# eCog102_uSD.net
KiCad netlist of a schematic drawn in EAGLE
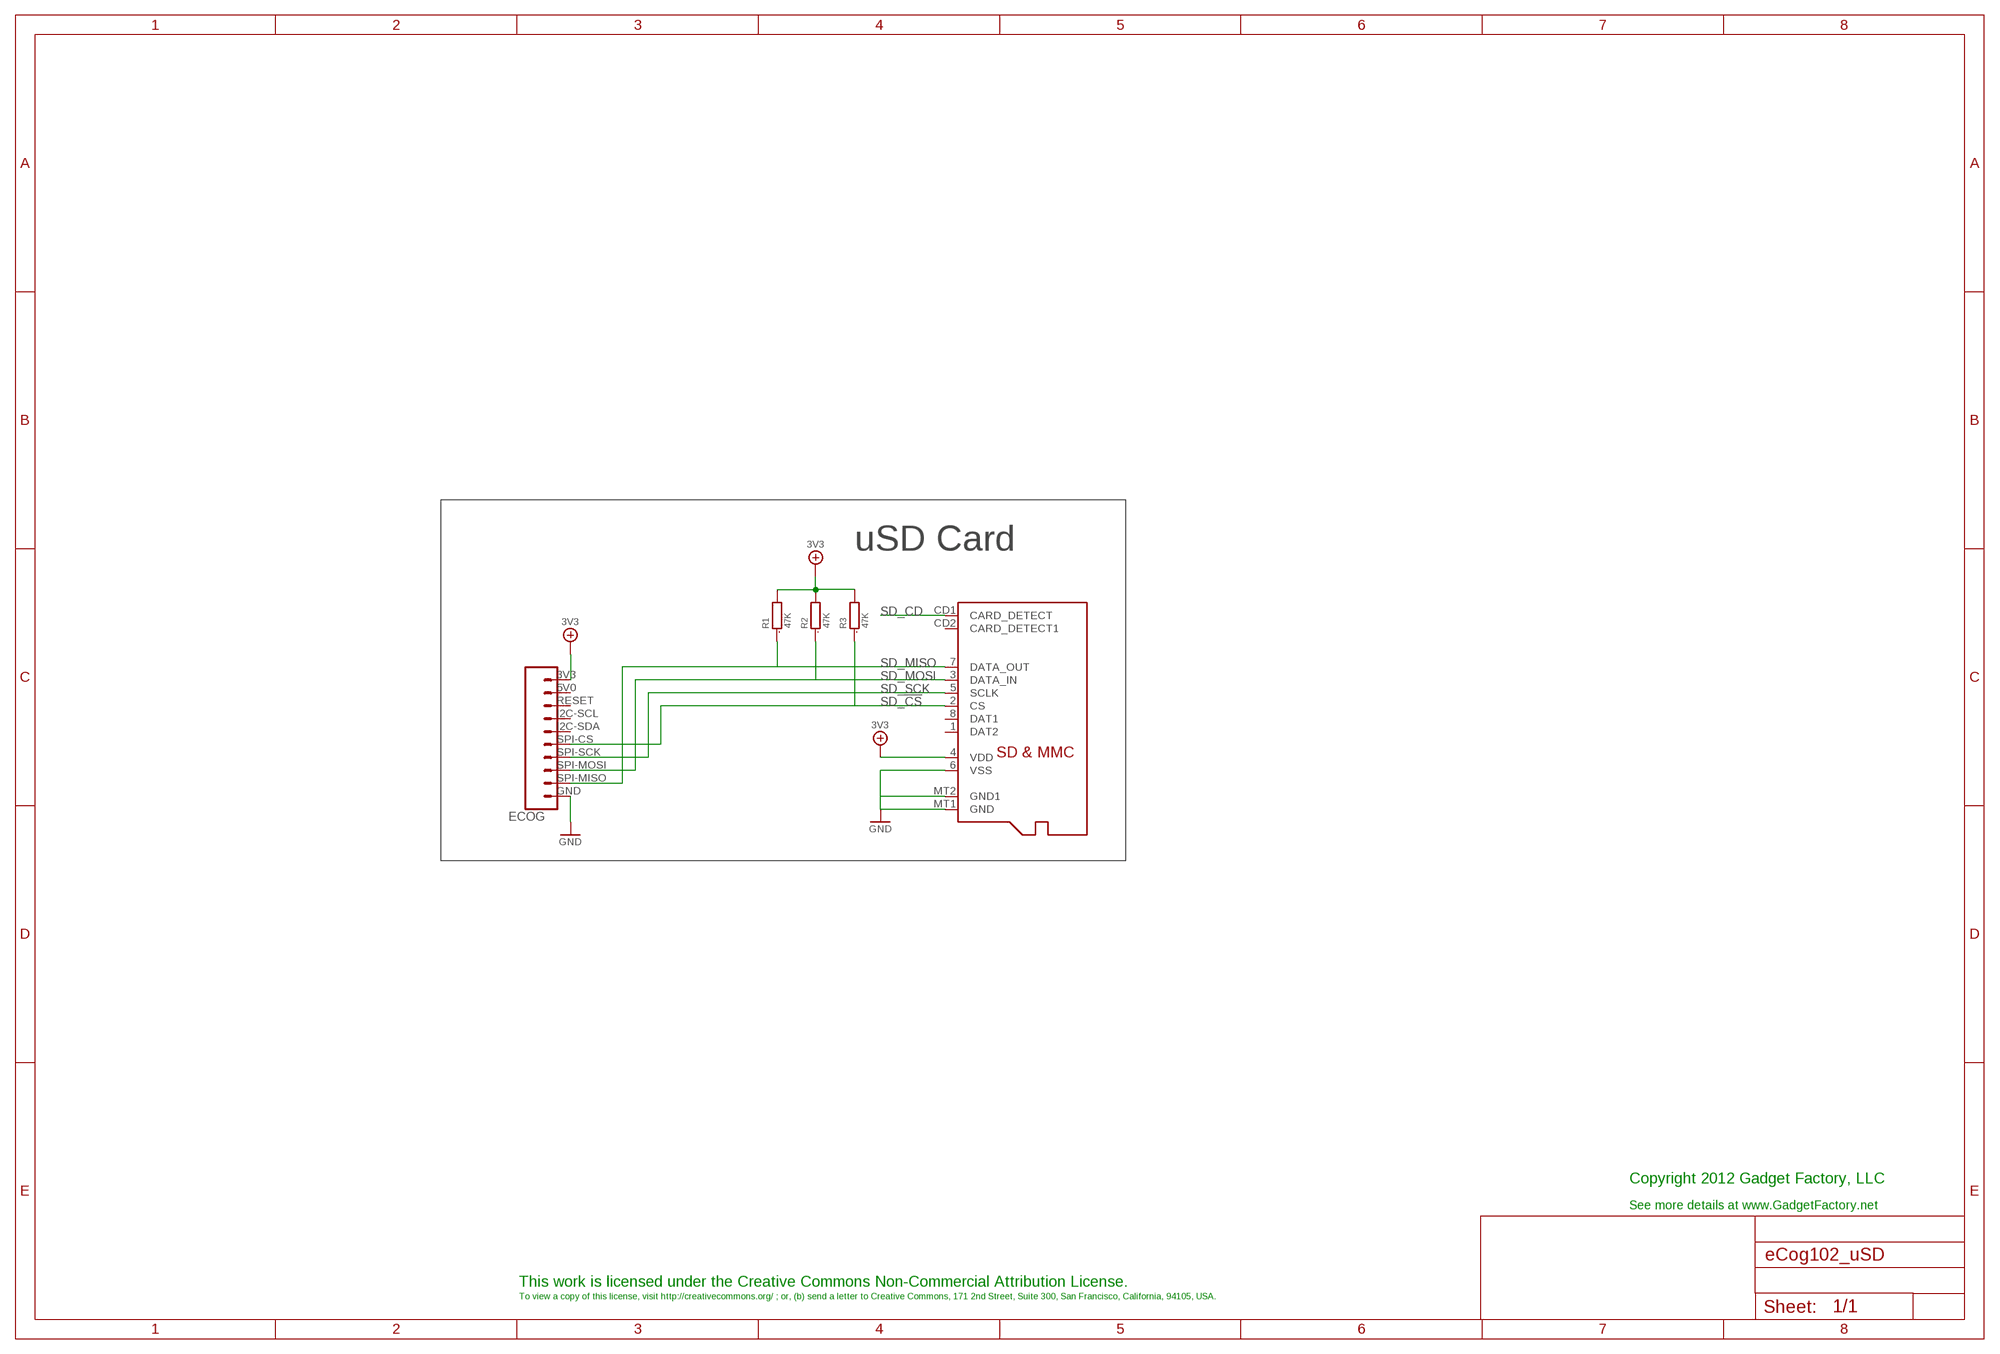
[diagram p0: schematic, sheet 1]

(export (version "E")
  (design (tool "Eeschema 10.0.6"))
  (components
    (comp (ref "ECOG")
      (value "ECOG_BUSES_ROWECOG_BUSES_SMD")
      (footprint "eagle-import:ECOG_BUSES_SMD")
      (libsource (lib "eagle-import") (part "ECOG_BUSES_ROWECOG_BUSES_SMD"))
    )
    (comp (ref "R1")
      (value "47K")
      (footprint "eagle-import:0805")
      (fields (field (name "PARTNO") "RMCF0805JT47K0"))
      (libsource (lib "eagle-import") (part "R0805"))
    )
    (comp (ref "R2")
      (value "47K")
      (footprint "eagle-import:0805")
      (fields (field (name "PARTNO") "RMCF0805JT47K0"))
      (libsource (lib "eagle-import") (part "R0805"))
    )
    (comp (ref "R3")
      (value "47K")
      (footprint "eagle-import:0805")
      (fields (field (name "PARTNO") "RMCF0805JT47K0"))
      (libsource (lib "eagle-import") (part "R0805"))
    )
    (comp (ref "SD1")
      (value "MICROSD")
      (footprint "eagle-import:MICROSD")
      (fields (field (name "DIGIKEY") "101-00660-68-6-1-ND") (field (name "PARTNO") "101-00660-68-6"))
      (libsource (lib "eagle-import") (part "MICROSD"))
    )
  )
  (nets
    (net (code "1") (name "/SD_CD") (class "Default")
      (node (ref "SD1") (pin "CD1") (pinfunction "CARD_DETECT_CD1") (pintype "passive"))
    )
    (net (code "2") (name "/SD_MISO") (class "Default")
      (node (ref "ECOG") (pin "SPI-MISO") (pinfunction "SPI-MISO_SPI-MISO") (pintype "passive"))
      (node (ref "R1") (pin "1") (pinfunction "1_1") (pintype "passive"))
      (node (ref "SD1") (pin "7") (pinfunction "DATA_OUT_7") (pintype "output"))
    )
    (net (code "3") (name "/SD_MOSI") (class "Default")
      (node (ref "ECOG") (pin "SPI-MOSI") (pinfunction "SPI-MOSI_SPI-MOSI") (pintype "passive"))
      (node (ref "R2") (pin "1") (pinfunction "1_1") (pintype "passive"))
      (node (ref "SD1") (pin "3") (pinfunction "DATA_IN_3") (pintype "input"))
    )
    (net (code "4") (name "/SD_SCK") (class "Default")
      (node (ref "ECOG") (pin "SPI-SCK") (pinfunction "SPI-SCK_SPI-SCK") (pintype "passive"))
      (node (ref "SD1") (pin "5") (pinfunction "SCLK_5") (pintype "input"))
    )
    (net (code "5") (name "/SD_~{CS}") (class "Default")
      (node (ref "ECOG") (pin "SPI-CS") (pinfunction "SPI-CS_SPI-CS") (pintype "passive"))
      (node (ref "R3") (pin "1") (pinfunction "1_1") (pintype "passive"))
      (node (ref "SD1") (pin "2") (pinfunction "CS_2") (pintype "input"))
    )
    (net (code "6") (name "3V3") (class "Default")
      (node (ref "ECOG") (pin "3V3") (pinfunction "3V3_3V3") (pintype "passive"))
      (node (ref "R1") (pin "2") (pinfunction "2_2") (pintype "passive"))
      (node (ref "R2") (pin "2") (pinfunction "2_2") (pintype "passive"))
      (node (ref "R3") (pin "2") (pinfunction "2_2") (pintype "passive"))
      (node (ref "SD1") (pin "4") (pinfunction "VDD_4") (pintype "power_in"))
    )
    (net (code "7") (name "GND") (class "Default")
      (node (ref "ECOG") (pin "GND") (pinfunction "GND_GND") (pintype "passive"))
      (node (ref "SD1") (pin "6") (pinfunction "VSS_6") (pintype "power_in"))
      (node (ref "SD1") (pin "MT1") (pinfunction "GND_MT1") (pintype "power_in"))
      (node (ref "SD1") (pin "MT2") (pinfunction "GND1_MT2") (pintype "power_in"))
    )
    (net (code "8") (name "unconnected-(ECOG-Pad5V0)") (class "Default")
      (node (ref "ECOG") (pin "5V0") (pinfunction "5V0_5V0") (pintype "passive"))
    )
    (net (code "9") (name "unconnected-(ECOG-PadI2C-SCL)") (class "Default")
      (node (ref "ECOG") (pin "I2C-SCL") (pinfunction "I2C-SCL_I2C-SCL") (pintype "passive"))
    )
    (net (code "10") (name "unconnected-(ECOG-PadI2C-SDA)") (class "Default")
      (node (ref "ECOG") (pin "I2C-SDA") (pinfunction "I2C-SDA_I2C-SDA") (pintype "passive"))
    )
    (net (code "11") (name "unconnected-(ECOG-PadRESET)") (class "Default")
      (node (ref "ECOG") (pin "RESET") (pinfunction "RESET_RESET") (pintype "passive"))
    )
    (net (code "12") (name "unconnected-(SD1-CARD_DETECT1-PadCD2)") (class "Default")
      (node (ref "SD1") (pin "CD2") (pinfunction "CARD_DETECT1_CD2") (pintype "passive"))
    )
    (net (code "13") (name "unconnected-(SD1-DAT1-Pad8)") (class "Default")
      (node (ref "SD1") (pin "8") (pinfunction "DAT1_8") (pintype "bidirectional"))
    )
    (net (code "14") (name "unconnected-(SD1-DAT2-Pad1)") (class "Default")
      (node (ref "SD1") (pin "1") (pinfunction "DAT2_1") (pintype "bidirectional"))
    )
  )
)
